# TeensyShield.net
KiCad netlist of a schematic drawn in EAGLE
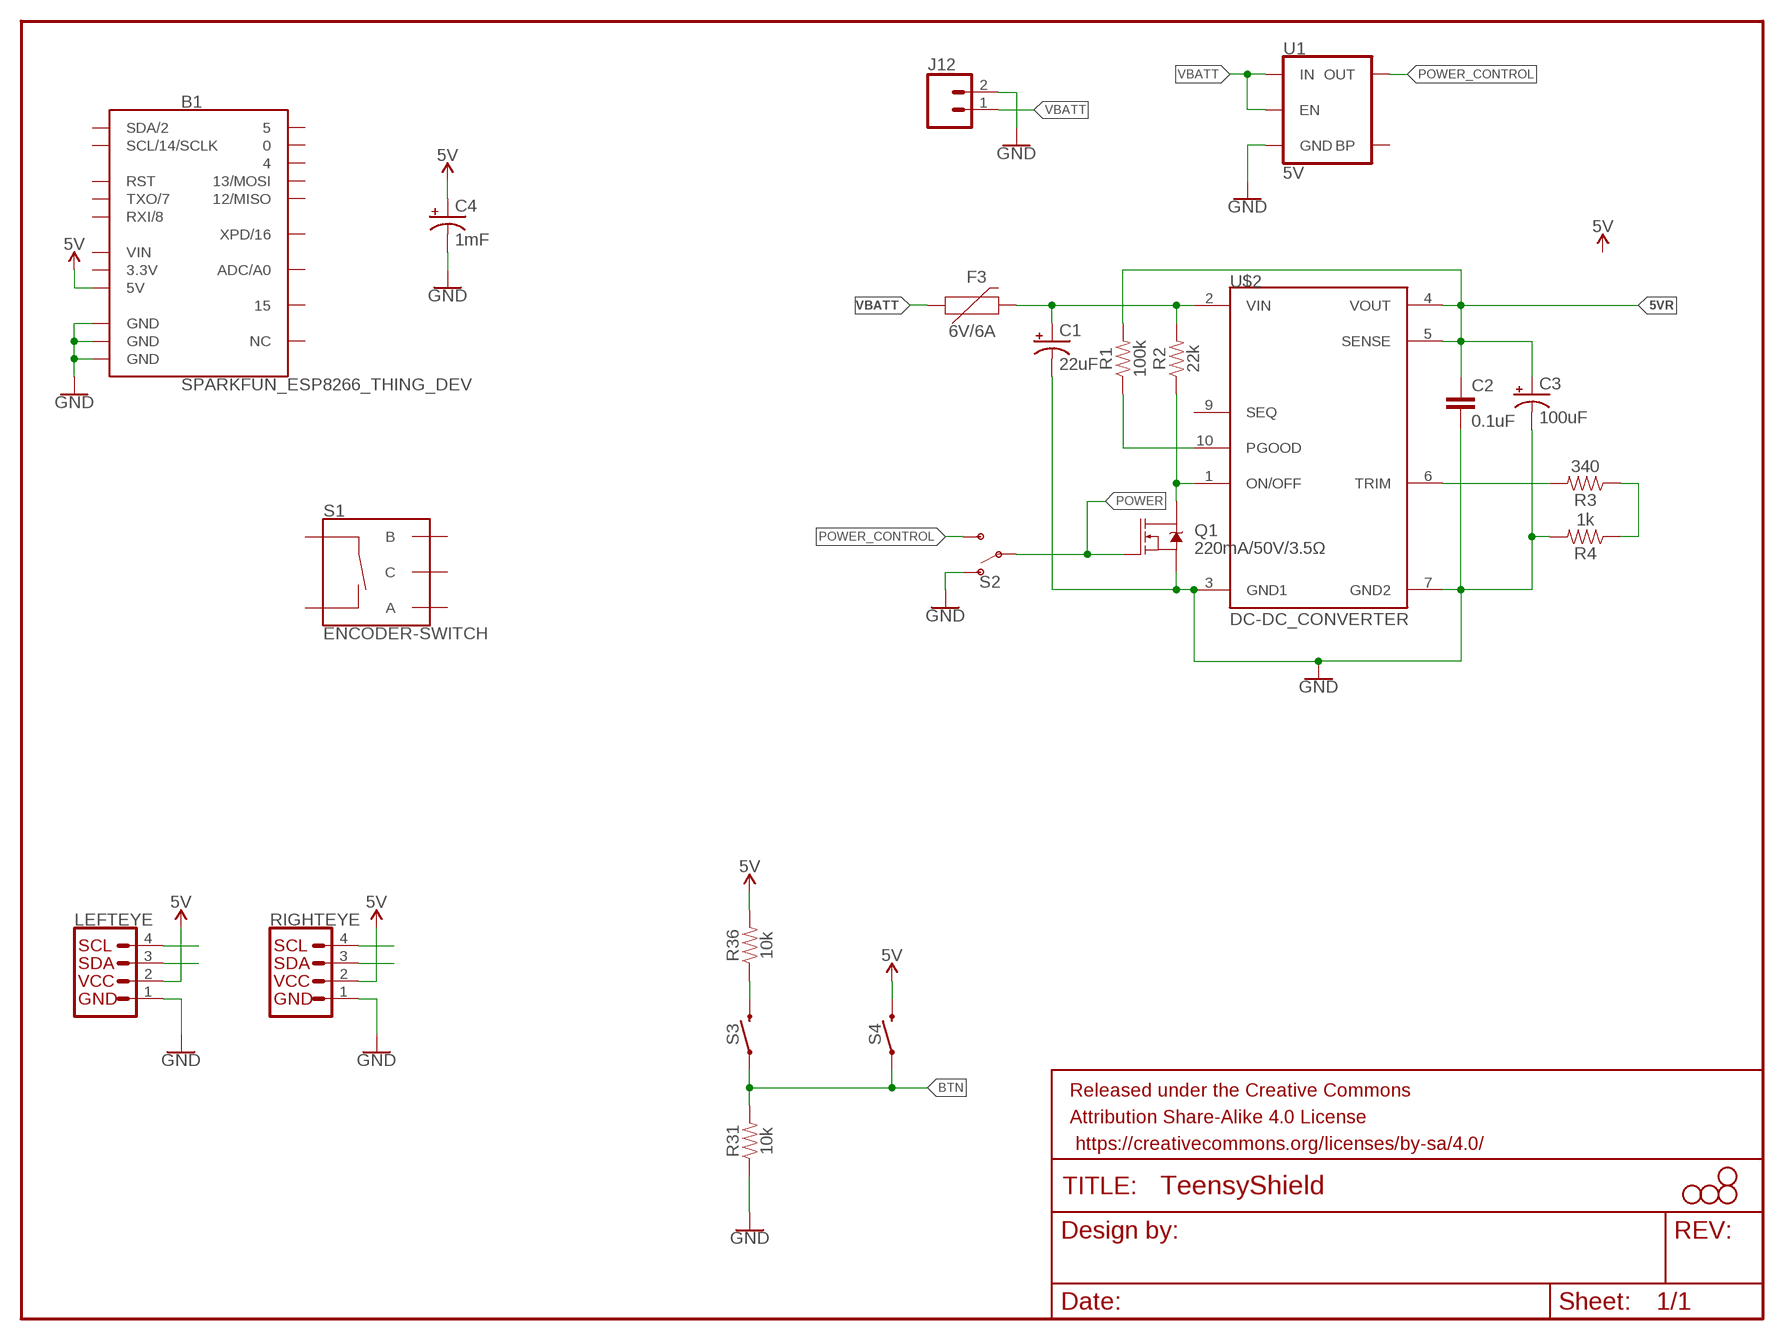
[diagram p0: schematic, sheet 1]

(export (version "E")
  (design (tool "Eeschema 10.0.6"))
  (components
    (comp (ref "B1")
      (value "SPARKFUN_ESP8266_THING_DEV")
      (footprint "eagle-import:SPARKFUN_ESP8266_THING_DEV")
      (libsource (lib "eagle-import") (part "SPARKFUN_ESP8266_THING_DEV"))
    )
    (comp (ref "C1")
      (value "22uF")
      (footprint "eagle-import:PANASONIC_C")
      (libsource (lib "eagle-import") (part "22UF-POLAR-PANASONIC_C-35V-20%"))
    )
    (comp (ref "C2")
      (value "0.1uF")
      (footprint "eagle-import:0603")
      (libsource (lib "eagle-import") (part "0.1UF-0603-25V-5%"))
    )
    (comp (ref "C3")
      (value "100uF")
      (footprint "eagle-import:PANASONIC_D")
      (libsource (lib "eagle-import") (part "100UF-POLAR-25V-20%(ELEC)"))
    )
    (comp (ref "C4")
      (value "1mF")
      (footprint "eagle-import:CPOL-RADIAL-5MM-10MM")
      (libsource (lib "eagle-import") (part "1000UF-RADIAL-5MM-25V-20%"))
    )
    (comp (ref "F3")
      (value "6V/6A")
      (footprint "eagle-import:1206")
      (libsource (lib "eagle-import") (part "PPTC_HALF-AMP"))
    )
    (comp (ref "FRAME1")
      (value "FRAME-LETTER")
      (footprint "eagle-import:CREATIVE_COMMONS")
      (libsource (lib "eagle-import") (part "FRAME-LETTER"))
    )
    (comp (ref "H3")
      (value "STAND-OFFTIGHT")
      (footprint "eagle-import:STAND-OFF-TIGHT")
      (libsource (lib "eagle-import") (part "STAND-OFFTIGHT"))
    )
    (comp (ref "H4")
      (value "STAND-OFFTIGHT")
      (footprint "eagle-import:STAND-OFF-TIGHT")
      (libsource (lib "eagle-import") (part "STAND-OFFTIGHT"))
    )
    (comp (ref "H5")
      (value "STAND-OFFTIGHT")
      (footprint "eagle-import:STAND-OFF-TIGHT")
      (libsource (lib "eagle-import") (part "STAND-OFFTIGHT"))
    )
    (comp (ref "H6")
      (value "STAND-OFFTIGHT")
      (footprint "eagle-import:STAND-OFF-TIGHT")
      (libsource (lib "eagle-import") (part "STAND-OFFTIGHT"))
    )
    (comp (ref "J12")
      (value "CONN_025MM")
      (footprint "eagle-import:SCREWTERMINAL-5MM-2")
      (libsource (lib "eagle-import") (part "CONN_025MM"))
    )
    (comp (ref "LEFTEYE")
      (value "QWIIC_CONNECTORJS-1MM")
      (footprint "eagle-import:1X04_1MM_RA")
      (libsource (lib "eagle-import") (part "QWIIC_CONNECTORJS-1MM"))
    )
    (comp (ref "Q1")
      (value "220mA/50V/3.5Ω")
      (footprint "eagle-import:SOT23-3")
      (libsource (lib "eagle-import") (part "MOSFET-NCH-BSS138"))
    )
    (comp (ref "R1")
      (value "100k")
      (footprint "eagle-import:0603")
      (libsource (lib "eagle-import") (part "100KOHM-0603-1/10W-1%"))
    )
    (comp (ref "R2")
      (value "22k")
      (footprint "eagle-import:0603")
      (libsource (lib "eagle-import") (part "22KOHM-0603-1/10W-1%"))
    )
    (comp (ref "R3")
      (value "340")
      (footprint "eagle-import:0603")
      (libsource (lib "eagle-import") (part "340OHM-0603-1/10W-1%"))
    )
    (comp (ref "R4")
      (value "1k")
      (footprint "eagle-import:0603")
      (libsource (lib "eagle-import") (part "1KOHM-0603-1/10W-1%"))
    )
    (comp (ref "R31")
      (value "10k")
      (footprint "eagle-import:0603")
      (libsource (lib "eagle-import") (part "10KOHM-0603-1/10W-1%"))
    )
    (comp (ref "R36")
      (value "10k")
      (footprint "eagle-import:0603")
      (libsource (lib "eagle-import") (part "10KOHM-0603-1/10W-1%"))
    )
    (comp (ref "RIGHTEYE")
      (value "QWIIC_CONNECTORJS-1MM")
      (footprint "eagle-import:1X04_1MM_RA")
      (libsource (lib "eagle-import") (part "QWIIC_CONNECTORJS-1MM"))
    )
    (comp (ref "S1")
      (value "ENCODER-SWITCH")
      (footprint "eagle-import:ROTARY_ENC_PLAIN")
      (libsource (lib "eagle-import") (part "ENCODER-SWITCH"))
    )
    (comp (ref "S2")
      (value "SWITCH-SPDT-SMD-RIGHT-ANGLE")
      (footprint "eagle-import:SWITCH_SPST_SMD_A")
      (libsource (lib "eagle-import") (part "SWITCH-SPDT-SMD-RIGHT-ANGLE"))
    )
    (comp (ref "S3")
      (value "MOMENTARY-SWITCH-SPST-PTH-RIGHT-ANGLE-KIT")
      (footprint "eagle-import:TACTILE_SWITCH_PTH_RIGHT_ANGLE_KIT")
      (libsource (lib "eagle-import") (part "MOMENTARY-SWITCH-SPST-PTH-RIGHT-ANGLE-KIT"))
    )
    (comp (ref "S4")
      (value "MOMENTARY-SWITCH-SPST-PTH-RIGHT-ANGLE-KIT")
      (footprint "eagle-import:TACTILE_SWITCH_PTH_RIGHT_ANGLE_KIT")
      (libsource (lib "eagle-import") (part "MOMENTARY-SWITCH-SPST-PTH-RIGHT-ANGLE-KIT"))
    )
    (comp (ref "U$2")
      (value "DC-DC_CONVERTER")
      (footprint "eagle-import:DC-DC_CONVERTER")
      (libsource (lib "eagle-import") (part "DC-DC_CONVERTER"))
    )
    (comp (ref "U1")
      (value "5V")
      (footprint "eagle-import:SOT23-5")
      (libsource (lib "eagle-import") (part "V_REG_MIC52055V"))
    )
  )
  (nets
    (net (code "1") (name "/3.3V") (class "Default")
      (node (ref "B1") (pin "3.3V") (pinfunction "3.3V_3.3V") (pintype "power_in"))
    )
    (net (code "2") (name "/VIN") (class "Default")
      (node (ref "B1") (pin "VIN") (pinfunction "VIN_VIN") (pintype "power_in"))
    )
    (net (code "3") (name "5V") (class "Default")
      (node (ref "B1") (pin "5V") (pinfunction "5V_5V") (pintype "power_in"))
      (node (ref "C4") (pin "+") (pinfunction "+_+") (pintype "passive"))
      (node (ref "LEFTEYE") (pin "2") (pinfunction "2_2") (pintype "power_in"))
      (node (ref "R36") (pin "2") (pinfunction "2_2") (pintype "passive"))
      (node (ref "RIGHTEYE") (pin "2") (pinfunction "2_2") (pintype "power_in"))
      (node (ref "S4") (pin "2") (pinfunction "2_2") (pintype "passive"))
    )
    (net (code "4") (name "5VR") (class "Default")
      (node (ref "C2") (pin "1") (pinfunction "1_1") (pintype "passive"))
      (node (ref "C3") (pin "+") (pinfunction "+_+") (pintype "passive"))
      (node (ref "R1") (pin "2") (pinfunction "2_2") (pintype "passive"))
      (node (ref "U$2") (pin "4") (pinfunction "VOUT_4") (pintype "bidirectional"))
      (node (ref "U$2") (pin "5") (pinfunction "SENSE_5") (pintype "bidirectional"))
    )
    (net (code "5") (name "BTN") (class "Default")
      (node (ref "R31") (pin "2") (pinfunction "2_2") (pintype "passive"))
      (node (ref "S3") (pin "1") (pinfunction "1_1") (pintype "passive"))
      (node (ref "S4") (pin "1") (pinfunction "1_1") (pintype "passive"))
    )
    (net (code "6") (name "GND") (class "Default")
      (node (ref "B1") (pin "GND@1") (pinfunction "GND_GND@1") (pintype "power_in"))
      (node (ref "B1") (pin "GND@2") (pinfunction "GND_GND@2") (pintype "power_in"))
      (node (ref "B1") (pin "GND@3") (pinfunction "GND_GND@3") (pintype "power_in"))
      (node (ref "C1") (pin "-") (pinfunction "-_-") (pintype "passive"))
      (node (ref "C2") (pin "2") (pinfunction "2_2") (pintype "passive"))
      (node (ref "C3") (pin "-") (pinfunction "-_-") (pintype "passive"))
      (node (ref "C4") (pin "-") (pinfunction "-_-") (pintype "passive"))
      (node (ref "J12") (pin "2") (pinfunction "2_2") (pintype "passive"))
      (node (ref "LEFTEYE") (pin "1") (pinfunction "1_1") (pintype "power_in"))
      (node (ref "Q1") (pin "2") (pinfunction "S_2") (pintype "bidirectional"))
      (node (ref "R31") (pin "1") (pinfunction "1_1") (pintype "passive"))
      (node (ref "R4") (pin "2") (pinfunction "2_2") (pintype "passive"))
      (node (ref "RIGHTEYE") (pin "1") (pinfunction "1_1") (pintype "power_in"))
      (node (ref "S2") (pin "1") (pinfunction "O_1") (pintype "passive"))
      (node (ref "U$2") (pin "3") (pinfunction "GND1_3") (pintype "bidirectional"))
      (node (ref "U$2") (pin "7") (pinfunction "GND2_7") (pintype "bidirectional"))
      (node (ref "U1") (pin "2") (pinfunction "GND_2") (pintype "input"))
    )
    (net (code "7") (name "Net-(Q1-D)") (class "Default")
      (node (ref "Q1") (pin "3") (pinfunction "D_3") (pintype "bidirectional"))
      (node (ref "R2") (pin "1") (pinfunction "1_1") (pintype "passive"))
      (node (ref "U$2") (pin "1") (pinfunction "ON/OFF_1") (pintype "bidirectional"))
    )
    (net (code "8") (name "Net-(R3-Pad1)") (class "Default")
      (node (ref "R3") (pin "1") (pinfunction "1_1") (pintype "passive"))
      (node (ref "R4") (pin "1") (pinfunction "1_1") (pintype "passive"))
    )
    (net (code "9") (name "Net-(R36-Pad1)") (class "Default")
      (node (ref "R36") (pin "1") (pinfunction "1_1") (pintype "passive"))
      (node (ref "S3") (pin "2") (pinfunction "2_2") (pintype "passive"))
    )
    (net (code "10") (name "Net-(U$2-PGOOD)") (class "Default")
      (node (ref "R1") (pin "1") (pinfunction "1_1") (pintype "passive"))
      (node (ref "U$2") (pin "10") (pinfunction "PGOOD_10") (pintype "bidirectional"))
    )
    (net (code "11") (name "Net-(U$2-TRIM)") (class "Default")
      (node (ref "R3") (pin "2") (pinfunction "2_2") (pintype "passive"))
      (node (ref "U$2") (pin "6") (pinfunction "TRIM_6") (pintype "bidirectional"))
    )
    (net (code "12") (name "Net-(U$2-VIN)") (class "Default")
      (node (ref "C1") (pin "+") (pinfunction "+_+") (pintype "passive"))
      (node (ref "F3") (pin "2") (pinfunction "2_2") (pintype "bidirectional"))
      (node (ref "R2") (pin "2") (pinfunction "2_2") (pintype "passive"))
      (node (ref "U$2") (pin "2") (pinfunction "VIN_2") (pintype "bidirectional"))
    )
    (net (code "13") (name "POWER") (class "Default")
      (node (ref "Q1") (pin "1") (pinfunction "G_1") (pintype "bidirectional"))
      (node (ref "S2") (pin "2") (pinfunction "P_2") (pintype "passive"))
    )
    (net (code "14") (name "POWER_CONTROL") (class "Default")
      (node (ref "S2") (pin "3") (pinfunction "S_3") (pintype "passive"))
      (node (ref "U1") (pin "5") (pinfunction "OUT_5") (pintype "passive"))
    )
    (net (code "15") (name "VBATT") (class "Default")
      (node (ref "F3") (pin "1") (pinfunction "1_1") (pintype "bidirectional"))
      (node (ref "J12") (pin "1") (pinfunction "1_1") (pintype "passive"))
      (node (ref "U1") (pin "1") (pinfunction "IN_1") (pintype "input"))
      (node (ref "U1") (pin "3") (pinfunction "EN_3") (pintype "input"))
    )
    (net (code "16") (name "unconnected-(B1-12{slash}MISO-Pad12)") (class "Default")
      (node (ref "B1") (pin "12") (pinfunction "12/MISO_12") (pintype "bidirectional"))
    )
    (net (code "17") (name "unconnected-(B1-13{slash}MOSI-Pad13)") (class "Default")
      (node (ref "B1") (pin "13") (pinfunction "13/MOSI_13") (pintype "bidirectional"))
    )
    (net (code "18") (name "unconnected-(B1-ADC{slash}A0-PadADC)") (class "Default")
      (node (ref "B1") (pin "ADC") (pinfunction "ADC/A0_ADC") (pintype "bidirectional"))
    )
    (net (code "19") (name "unconnected-(B1-Pad0)") (class "Default")
      (node (ref "B1") (pin "0") (pinfunction "0_0") (pintype "bidirectional"))
    )
    (net (code "20") (name "unconnected-(B1-Pad4)") (class "Default")
      (node (ref "B1") (pin "4") (pinfunction "4_4") (pintype "bidirectional"))
    )
    (net (code "21") (name "unconnected-(B1-Pad5)") (class "Default")
      (node (ref "B1") (pin "5") (pinfunction "5_5") (pintype "bidirectional"))
    )
    (net (code "22") (name "unconnected-(B1-Pad15)") (class "Default")
      (node (ref "B1") (pin "15") (pinfunction "15_15") (pintype "bidirectional"))
    )
    (net (code "23") (name "unconnected-(B1-PadNC)") (class "Default")
      (node (ref "B1") (pin "NC") (pinfunction "NC_NC") (pintype "no_connect"))
    )
    (net (code "24") (name "unconnected-(B1-PadRST)") (class "Default")
      (node (ref "B1") (pin "RST") (pinfunction "RST_RST") (pintype "input"))
    )
    (net (code "25") (name "unconnected-(B1-RXI{slash}8-PadRX)") (class "Default")
      (node (ref "B1") (pin "RX") (pinfunction "RXI/8_RX") (pintype "input"))
    )
    (net (code "26") (name "unconnected-(B1-SCL{slash}14{slash}SCLK-Pad14)") (class "Default")
      (node (ref "B1") (pin "14") (pinfunction "SCL/14/SCLK_14") (pintype "bidirectional"))
    )
    (net (code "27") (name "unconnected-(B1-SDA{slash}2-Pad2)") (class "Default")
      (node (ref "B1") (pin "2") (pinfunction "SDA/2_2") (pintype "bidirectional"))
    )
    (net (code "28") (name "unconnected-(B1-TXO{slash}7-PadTX)") (class "Default")
      (node (ref "B1") (pin "TX") (pinfunction "TXO/7_TX") (pintype "output"))
    )
    (net (code "29") (name "unconnected-(B1-XPD{slash}16-Pad16)") (class "Default")
      (node (ref "B1") (pin "16") (pinfunction "XPD/16_16") (pintype "bidirectional"))
    )
    (net (code "30") (name "unconnected-(LEFTEYE-Pad3)") (class "Default")
      (node (ref "LEFTEYE") (pin "3") (pinfunction "3_3") (pintype "passive"))
    )
    (net (code "31") (name "unconnected-(LEFTEYE-Pad4)") (class "Default")
      (node (ref "LEFTEYE") (pin "4") (pinfunction "4_4") (pintype "passive"))
    )
    (net (code "32") (name "unconnected-(RIGHTEYE-Pad3)") (class "Default")
      (node (ref "RIGHTEYE") (pin "3") (pinfunction "3_3") (pintype "passive"))
    )
    (net (code "33") (name "unconnected-(RIGHTEYE-Pad4)") (class "Default")
      (node (ref "RIGHTEYE") (pin "4") (pinfunction "4_4") (pintype "passive"))
    )
    (net (code "34") (name "unconnected-(S1-PadA)") (class "Default")
      (node (ref "S1") (pin "A") (pinfunction "A_A") (pintype "bidirectional"))
    )
    (net (code "35") (name "unconnected-(S1-PadB)") (class "Default")
      (node (ref "S1") (pin "B") (pinfunction "B_B") (pintype "bidirectional"))
    )
    (net (code "36") (name "unconnected-(S1-PadC)") (class "Default")
      (node (ref "S1") (pin "C") (pinfunction "C_C") (pintype "bidirectional"))
    )
    (net (code "37") (name "unconnected-(S1-PadSW+)") (class "Default")
      (node (ref "S1") (pin "SW+") (pinfunction "SW+_SW+") (pintype "bidirectional"))
    )
    (net (code "38") (name "unconnected-(S1-PadSW-)") (class "Default")
      (node (ref "S1") (pin "SW-") (pinfunction "SW-_SW-") (pintype "bidirectional"))
    )
    (net (code "39") (name "unconnected-(U$2-SEQ-Pad9)") (class "Default")
      (node (ref "U$2") (pin "9") (pinfunction "SEQ_9") (pintype "bidirectional"))
    )
    (net (code "40") (name "unconnected-(U1-BP-Pad4)") (class "Default")
      (node (ref "U1") (pin "4") (pinfunction "BP_4") (pintype "input"))
    )
  )
)
